# preamp_chanel2_normal.net
KiCad netlist of a schematic drawn in Altium Designer
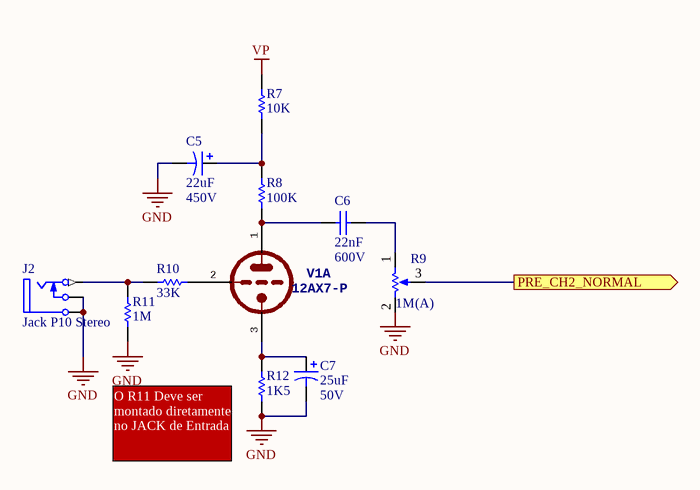
[diagram p0: preamp_chanel2_normal.SchDoc]

(export (version "E")
  (design (tool "Eeschema 10.0.6"))
  (components
    (comp (ref "C5")
      (value "22uF")
      (footprint "RAD-POL-7.6-15")
      (description "Polarized Capacitor (Axial)")
      (fields
        (field (name "VOLTAGE") "450V")
        (field (name "Comment") "Cap Pol Rad")
        (field (name "PUBLISHER") "Altium Limited")
      )
      (libsource (lib "capacitors") (part "Cap Pol Rad"))
    )
    (comp (ref "C6")
      (value "22nF")
      (footprint "ORANGE-DROP-100nF")
      (description "Capacitor")
      (fields
        (field (name "VOLTAGE") "600V")
        (field (name "Comment") "Orange Drop Capacitor")
        (field (name "PUBLISHER") "Altium Limited")
      )
      (libsource (lib "capacitors") (part "Cap-Orange-DROP-22nF-600V"))
    )
    (comp (ref "C7")
      (value "25uF")
      (footprint "AXIAL-POL-30mm")
      (description "Polarized Capacitor Axial")
      (fields
        (field (name "VOLTAGE") "50V")
        (field (name "Comment") "Cap Pol Axial")
        (field (name "PUBLISHER") "Whitesheep Amps")
      )
      (libsource (lib "capacitors") (part "Cap Pol Axial"))
    )
    (comp (ref "J2")
      (value "Jack P10 Stereo")
      (footprint "JACK-STEREO-3PAD")
      (description "Jack Socket, 1/4\" [6.5mm], Thru-Hole, Vertical, 2-Conductor with Tip closed")
      (fields (field (name "PUBLISHER") "Altium Limited"))
      (libsource (lib "jacks") (part "Jack P10 Stereo"))
    )
    (comp (ref "R7")
      (value "10K")
      (footprint "AXIAL-0.6")
      (description "Semiconductor Resistor")
      (fields
        (field (name "POWER") "1/2W")
        (field (name "Comment") "Metal Film Resistor 1/2W")
        (field (name "PUBLISHER") "Whitesheep Amps")
      )
      (libsource (lib "resistors") (part "Res Metal Film 1/2W"))
    )
    (comp (ref "R8")
      (value "100K")
      (footprint "AXIAL-0.6")
      (description "Semiconductor Resistor")
      (fields
        (field (name "POWER") "1/2W")
        (field (name "Comment") "Metal Film Resistor 1/2W")
        (field (name "PUBLISHER") "Whitesheep Amps")
      )
      (libsource (lib "resistors") (part "Res Metal Film 1/2W"))
    )
    (comp (ref "R9")
      (value "1M")
      (footprint "pot_alpha - 2.54mm")
      (description "Potentiometer")
      (fields
        (field (name "TYPE") "(A)")
        (field (name "Comment") "ALPHA Potentiometer")
        (field (name "PUBLISHER") "Altium Limited")
      )
      (libsource (lib "potentiometers") (part "alpha-pot"))
    )
    (comp (ref "R10")
      (value "33K")
      (footprint "AXIAL-0.6")
      (description "Semiconductor Resistor")
      (fields
        (field (name "POWER") "1/2W")
        (field (name "Comment") "Metal Film Resistor 1/2W")
        (field (name "PUBLISHER") "Whitesheep Amps")
      )
      (libsource (lib "resistors") (part "Res Metal Film 1/2W"))
    )
    (comp (ref "R11")
      (value "1M")
      (footprint "AXIAL-0.6")
      (description "Semiconductor Resistor")
      (fields
        (field (name "POWER") "1/2W")
        (field (name "Comment") "Metal Film Resistor 1/2W")
        (field (name "PUBLISHER") "Whitesheep Amps")
      )
      (libsource (lib "resistors") (part "Res Metal Film 1/2W"))
    )
    (comp (ref "R12")
      (value "1K5")
      (footprint "AXIAL-0.6")
      (description "Semiconductor Resistor")
      (fields
        (field (name "POWER") "1/2W")
        (field (name "Comment") "Metal Film Resistor 1/2W")
        (field (name "PUBLISHER") "Whitesheep Amps")
      )
      (libsource (lib "resistors") (part "Res Metal Film 1/2W"))
    )
    (comp (ref "V1")
      (value "12AX7-P")
      (footprint "NOVAL")
      (libsource (lib "eagle_tubes_v6") (part "12AX7-P"))
    )
  )
  (nets
    (net (code "1") (name "/PRE_CH2_NORMAL") (class "Default")
      (node (ref "R9") (pin "3") (pinfunction "TAP_3") (pintype "passive"))
    )
    (net (code "2") (name "GND") (class "Default")
      (node (ref "C5") (pin "2") (pinfunction "2_2") (pintype "passive"))
      (node (ref "C7") (pin "2") (pinfunction "2_2") (pintype "passive"))
      (node (ref "J2") (pin "2") (pinfunction "TN_2") (pintype "passive"))
      (node (ref "J2") (pin "5") (pinfunction "S_5") (pintype "power_in"))
      (node (ref "R11") (pin "1") (pinfunction "1_1") (pintype "passive"))
      (node (ref "R12") (pin "1") (pinfunction "1_1") (pintype "passive"))
      (node (ref "R9") (pin "2") (pinfunction "BOT_2") (pintype "passive"))
    )
    (net (code "3") (name "Net-(C5-Pad1)") (class "Default")
      (node (ref "C5") (pin "1") (pinfunction "1_1") (pintype "passive"))
      (node (ref "R7") (pin "1") (pinfunction "1_1") (pintype "passive"))
      (node (ref "R8") (pin "2") (pinfunction "2_2") (pintype "passive"))
    )
    (net (code "4") (name "Net-(J2-T)") (class "Default")
      (node (ref "J2") (pin "1") (pinfunction "T_1") (pintype "output"))
      (node (ref "R10") (pin "2") (pinfunction "2_2") (pintype "passive"))
      (node (ref "R11") (pin "2") (pinfunction "2_2") (pintype "passive"))
    )
    (net (code "5") (name "Net-(R9-TOP)") (class "Default")
      (node (ref "C6") (pin "2") (pinfunction "2_2") (pintype "passive"))
      (node (ref "R9") (pin "1") (pinfunction "TOP_1") (pintype "passive"))
    )
    (net (code "6") (name "Net-(V1A-TA)") (class "Default")
      (node (ref "C6") (pin "1") (pinfunction "1_1") (pintype "passive"))
      (node (ref "R8") (pin "1") (pinfunction "1_1") (pintype "passive"))
      (node (ref "V1") (pin "1") (pinfunction "TA_1") (pintype "passive"))
    )
    (net (code "7") (name "Net-(V1A-TG)") (class "Default")
      (node (ref "R10") (pin "1") (pinfunction "1_1") (pintype "passive"))
      (node (ref "V1") (pin "2") (pinfunction "TG_2") (pintype "passive"))
    )
    (net (code "8") (name "Net-(V1A-TK)") (class "Default")
      (node (ref "C7") (pin "1") (pinfunction "1_1") (pintype "passive"))
      (node (ref "R12") (pin "2") (pinfunction "2_2") (pintype "passive"))
      (node (ref "V1") (pin "3") (pinfunction "TK_3") (pintype "passive"))
    )
    (net (code "9") (name "VP") (class "Default")
      (node (ref "R7") (pin "2") (pinfunction "2_2") (pintype "passive"))
    )
  )
)
